# Versino1.net
KiCad netlist of a schematic drawn in EAGLE
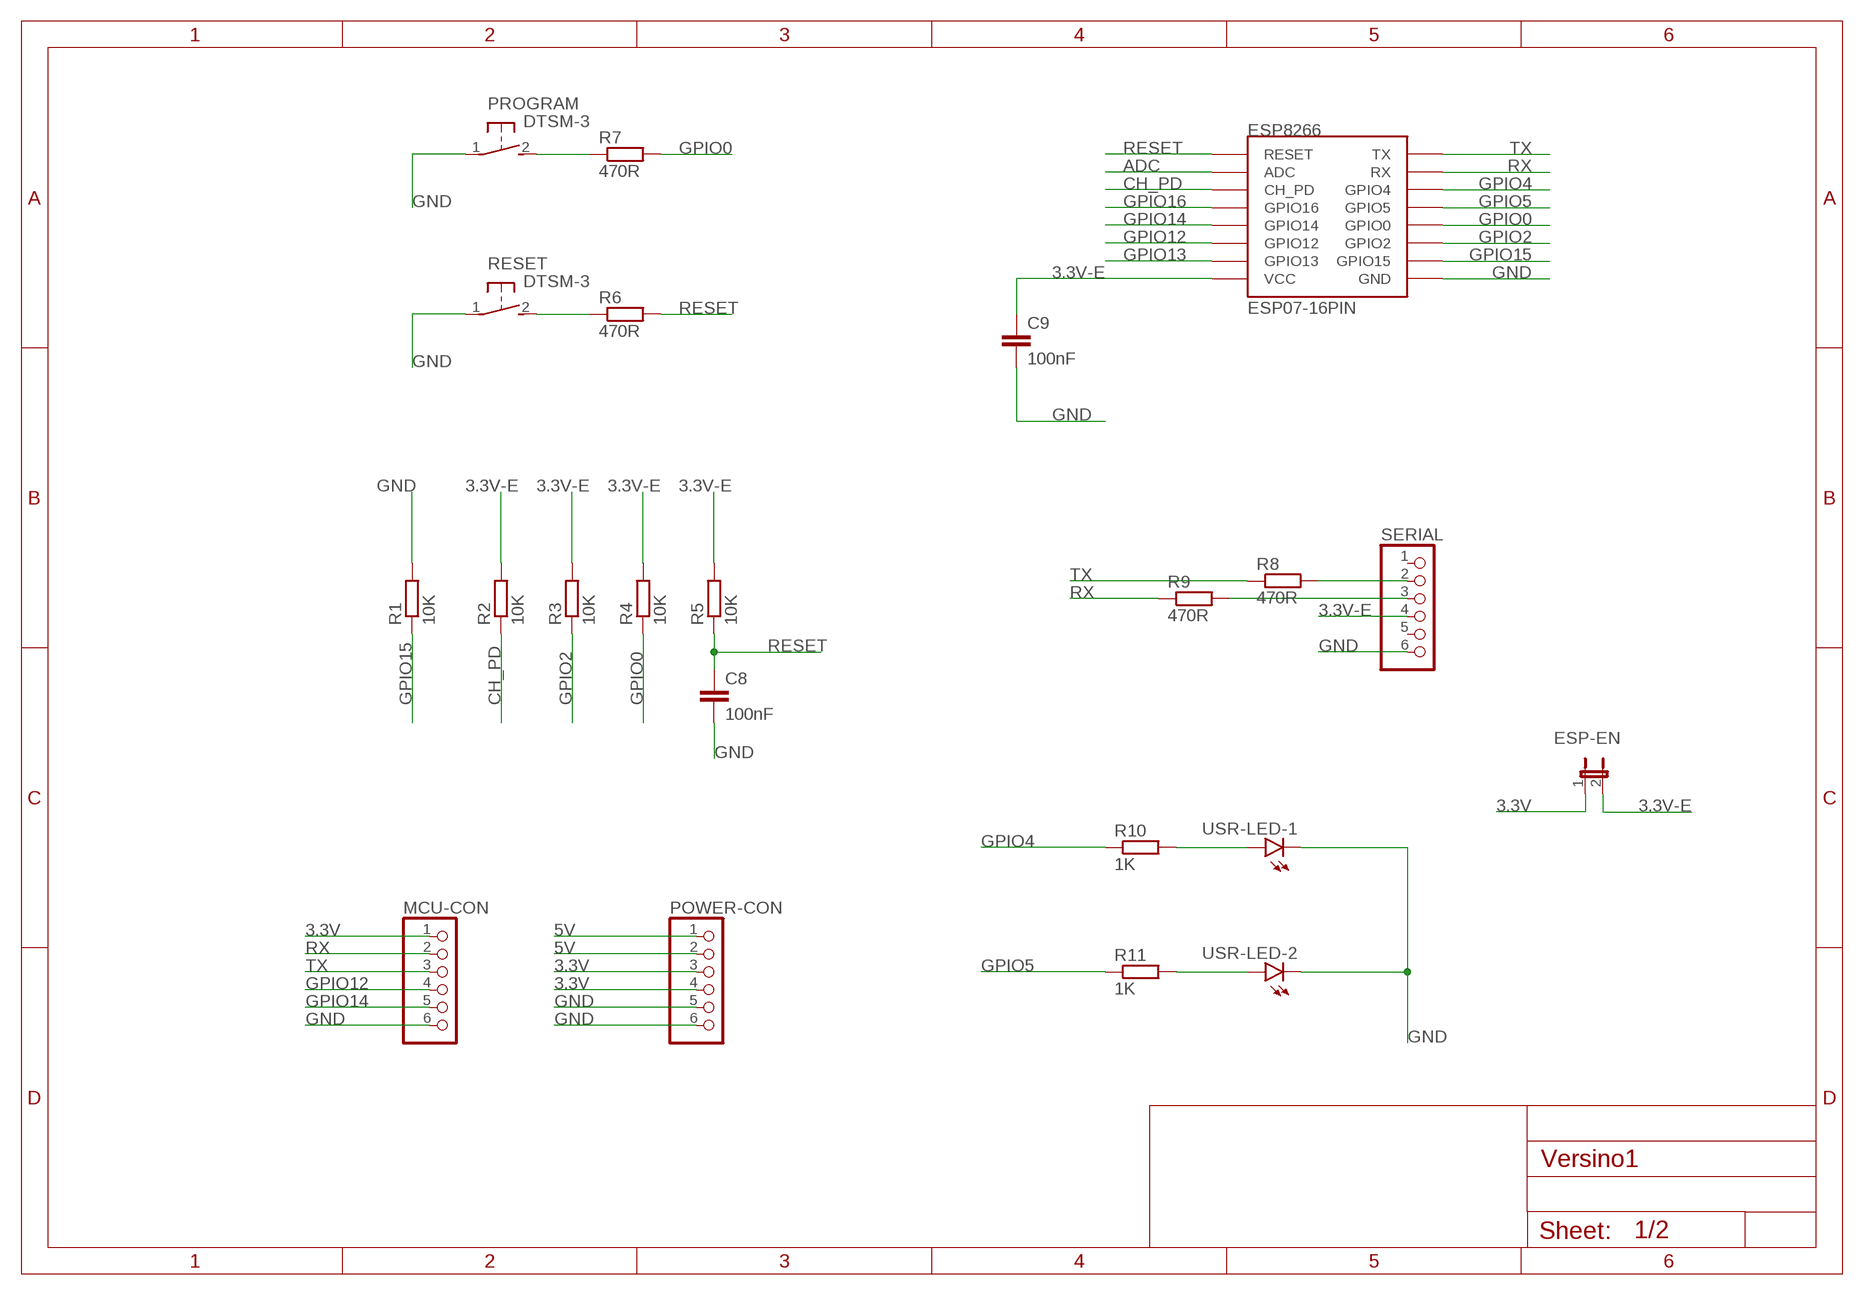
[diagram p0: schematic, sheet 1]
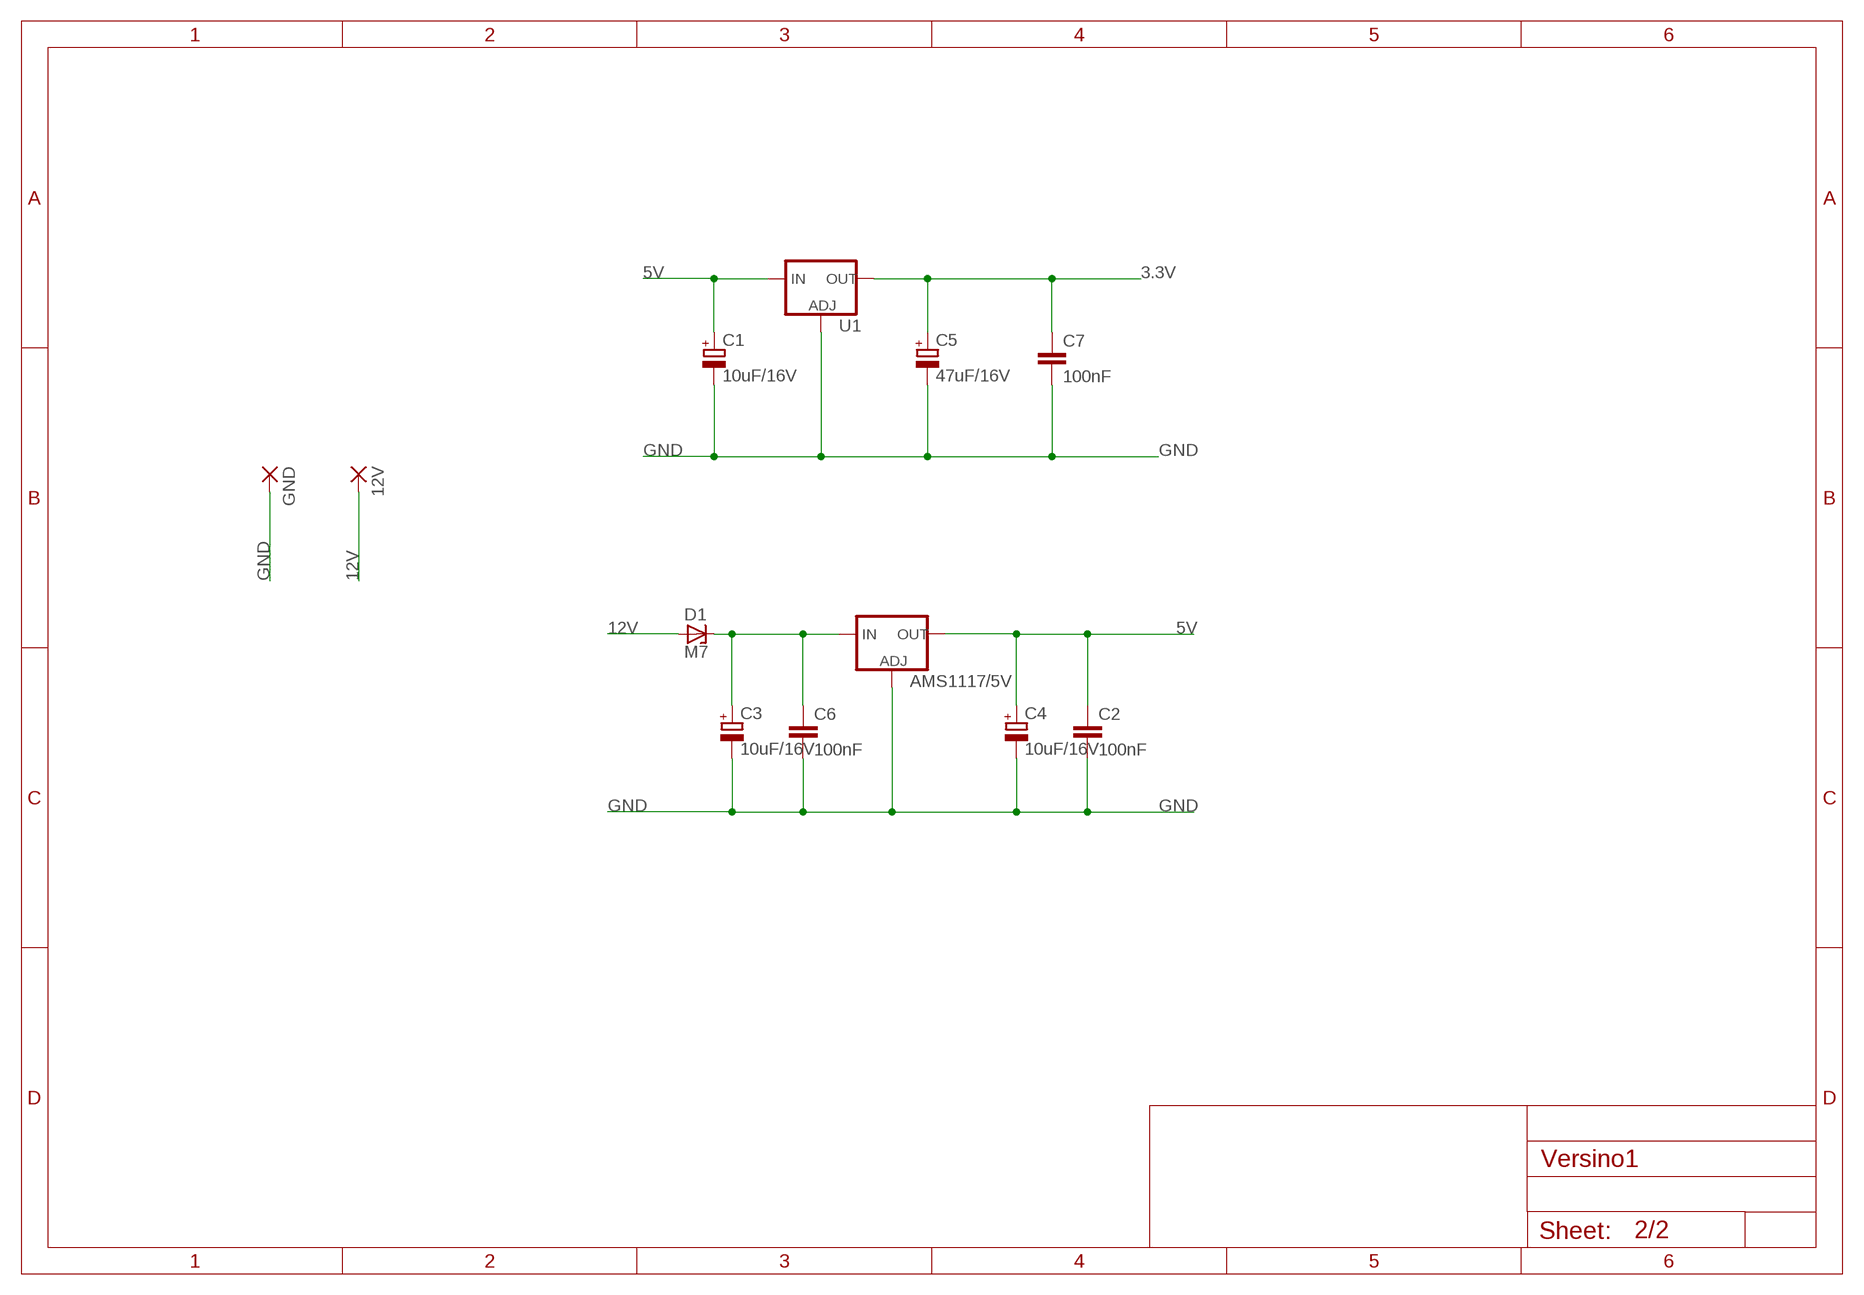
[diagram p1: schematic, sheet 2]

(export (version "E")
  (design (tool "Eeschema 10.0.6"))
  (components
    (comp (ref "12V")
      (value "SMD5")
      (footprint "eagle-import:SMD2,54-5,08")
      (libsource (lib "eagle-import") (part "SMD5"))
    )
    (comp (ref "AMS1117/5V")
      (value "V_REG_LM1117SOT223")
      (footprint "eagle-import:SOT223")
      (libsource (lib "eagle-import") (part "V_REG_LM1117SOT223"))
    )
    (comp (ref "C1")
      (value "10uF/16V")
      (footprint "eagle-import:SMC_B")
      (libsource (lib "eagle-import") (part "CPOL-EUSMCB"))
    )
    (comp (ref "C2")
      (value "100nF")
      (footprint "eagle-import:C0603")
      (libsource (lib "eagle-import") (part "C-EUC0603"))
    )
    (comp (ref "C3")
      (value "10uF/16V")
      (footprint "eagle-import:SMC_B")
      (libsource (lib "eagle-import") (part "CPOL-EUSMCB"))
    )
    (comp (ref "C4")
      (value "10uF/16V")
      (footprint "eagle-import:SMC_B")
      (libsource (lib "eagle-import") (part "CPOL-EUSMCB"))
    )
    (comp (ref "C5")
      (value "47uF/16V")
      (footprint "eagle-import:SMC_B")
      (libsource (lib "eagle-import") (part "CPOL-EUSMCB"))
    )
    (comp (ref "C6")
      (value "100nF")
      (footprint "eagle-import:C0603")
      (libsource (lib "eagle-import") (part "C-EUC0603"))
    )
    (comp (ref "C7")
      (value "100nF")
      (footprint "eagle-import:C0603")
      (libsource (lib "eagle-import") (part "C-EUC0603"))
    )
    (comp (ref "D1")
      (value "M7")
      (footprint "eagle-import:DO214AC")
      (fields (field (name "MF") "ON Semiconductor") (field (name "MPN") "1SMA5913BT3G"))
      (libsource (lib "eagle-import") (part "1SMA59BT3G13"))
    )
    (comp (ref "GND")
      (value "SMD5")
      (footprint "eagle-import:SMD2,54-5,08")
      (libsource (lib "eagle-import") (part "SMD5"))
    )
    (comp (ref "U1")
      (value "V_REG_LM1117SOT223")
      (footprint "eagle-import:SOT223")
      (libsource (lib "eagle-import") (part "V_REG_LM1117SOT223"))
    )
    (comp (ref "C8")
      (value "100nF")
      (footprint "eagle-import:C0603")
      (libsource (lib "eagle-import") (part "C-EUC0603"))
    )
    (comp (ref "C9")
      (value "100nF")
      (footprint "eagle-import:C0603")
      (libsource (lib "eagle-import") (part "C-EUC0603"))
    )
    (comp (ref "ESP-EN")
      (value "JP1E")
      (footprint "eagle-import:JP1")
      (libsource (lib "eagle-import") (part "JP1E"))
    )
    (comp (ref "ESP8266")
      (value "ESP07-16PIN")
      (footprint "eagle-import:ESP07-16PIN")
      (libsource (lib "eagle-import") (part "ESP07-16PIN"))
    )
    (comp (ref "MCU-CON")
      (value "PINHD-1X6")
      (footprint "eagle-import:1X06")
      (libsource (lib "eagle-import") (part "PINHD-1X6"))
    )
    (comp (ref "POWER-CON")
      (value "PINHD-1X6")
      (footprint "eagle-import:1X06")
      (libsource (lib "eagle-import") (part "PINHD-1X6"))
    )
    (comp (ref "PROGRAM")
      (value "DTSM-3")
      (footprint "eagle-import:DTSM-3")
      (libsource (lib "eagle-import") (part "DTSM-3"))
    )
    (comp (ref "R1")
      (value "10K")
      (footprint "eagle-import:R0603")
      (libsource (lib "eagle-import") (part "R-EU_R0603"))
    )
    (comp (ref "R2")
      (value "10K")
      (footprint "eagle-import:R0603")
      (libsource (lib "eagle-import") (part "R-EU_R0603"))
    )
    (comp (ref "R3")
      (value "10K")
      (footprint "eagle-import:R0603")
      (libsource (lib "eagle-import") (part "R-EU_R0603"))
    )
    (comp (ref "R4")
      (value "10K")
      (footprint "eagle-import:R0603")
      (libsource (lib "eagle-import") (part "R-EU_R0603"))
    )
    (comp (ref "R5")
      (value "10K")
      (footprint "eagle-import:R0603")
      (libsource (lib "eagle-import") (part "R-EU_R0603"))
    )
    (comp (ref "R6")
      (value "470R")
      (footprint "eagle-import:R0603")
      (libsource (lib "eagle-import") (part "R-EU_R0603"))
    )
    (comp (ref "R7")
      (value "470R")
      (footprint "eagle-import:R0603")
      (libsource (lib "eagle-import") (part "R-EU_R0603"))
    )
    (comp (ref "R8")
      (value "470R")
      (footprint "eagle-import:R0603")
      (libsource (lib "eagle-import") (part "R-EU_R0603"))
    )
    (comp (ref "R9")
      (value "470R")
      (footprint "eagle-import:R0603")
      (libsource (lib "eagle-import") (part "R-EU_R0603"))
    )
    (comp (ref "R10")
      (value "1K")
      (footprint "eagle-import:R0603")
      (libsource (lib "eagle-import") (part "R-EU_R0603"))
    )
    (comp (ref "R11")
      (value "1K")
      (footprint "eagle-import:R0603")
      (libsource (lib "eagle-import") (part "R-EU_R0603"))
    )
    (comp (ref "RESET")
      (value "DTSM-3")
      (footprint "eagle-import:DTSM-3")
      (libsource (lib "eagle-import") (part "DTSM-3"))
    )
    (comp (ref "SERIAL")
      (value "PINHD-1X6")
      (footprint "eagle-import:1X06")
      (libsource (lib "eagle-import") (part "PINHD-1X6"))
    )
    (comp (ref "USR-LED-1")
      (value "LEDCHIP-LED0805")
      (footprint "eagle-import:CHIP-LED0805")
      (libsource (lib "eagle-import") (part "LEDCHIP-LED0805"))
    )
    (comp (ref "USR-LED-2")
      (value "LEDCHIP-LED0805")
      (footprint "eagle-import:CHIP-LED0805")
      (libsource (lib "eagle-import") (part "LEDCHIP-LED0805"))
    )
  )
  (nets
    (net (code "1") (name "3.3V") (class "Default")
      (node (ref "C5") (pin "+") (pinfunction "+_+") (pintype "passive"))
      (node (ref "C7") (pin "1") (pinfunction "1_1") (pintype "passive"))
      (node (ref "ESP-EN") (pin "1") (pinfunction "1_1") (pintype "passive"))
      (node (ref "MCU-CON") (pin "1") (pinfunction "1_1") (pintype "passive"))
      (node (ref "POWER-CON") (pin "3") (pinfunction "3_3") (pintype "passive"))
      (node (ref "POWER-CON") (pin "4") (pinfunction "4_4") (pintype "passive"))
      (node (ref "U1") (pin "2") (pinfunction "OUT_2") (pintype "output"))
      (node (ref "U1") (pin "4") (pinfunction "OUT_4") (pintype "output"))
    )
    (net (code "2") (name "3.3V-E") (class "Default")
      (node (ref "C9") (pin "1") (pinfunction "1_1") (pintype "passive"))
      (node (ref "ESP-EN") (pin "2") (pinfunction "2_2") (pintype "passive"))
      (node (ref "ESP8266") (pin "VCC") (pinfunction "VCC_VCC") (pintype "bidirectional"))
      (node (ref "R2") (pin "2") (pinfunction "2_2") (pintype "passive"))
      (node (ref "R3") (pin "2") (pinfunction "2_2") (pintype "passive"))
      (node (ref "R4") (pin "2") (pinfunction "2_2") (pintype "passive"))
      (node (ref "R5") (pin "2") (pinfunction "2_2") (pintype "passive"))
      (node (ref "SERIAL") (pin "4") (pinfunction "4_4") (pintype "passive"))
    )
    (net (code "3") (name "5V") (class "Default")
      (node (ref "AMS1117/5V") (pin "2") (pinfunction "OUT_2") (pintype "output"))
      (node (ref "AMS1117/5V") (pin "4") (pinfunction "OUT_4") (pintype "output"))
      (node (ref "C1") (pin "+") (pinfunction "+_+") (pintype "passive"))
      (node (ref "C2") (pin "1") (pinfunction "1_1") (pintype "passive"))
      (node (ref "C4") (pin "+") (pinfunction "+_+") (pintype "passive"))
      (node (ref "POWER-CON") (pin "1") (pinfunction "1_1") (pintype "passive"))
      (node (ref "POWER-CON") (pin "2") (pinfunction "2_2") (pintype "passive"))
      (node (ref "U1") (pin "3") (pinfunction "IN_3") (pintype "input"))
    )
    (net (code "4") (name "12V") (class "Default")
      (node (ref "12V") (pin "1") (pinfunction "P_1") (pintype "passive"))
      (node (ref "D1") (pin "A") (pinfunction "A_A") (pintype "passive"))
    )
    (net (code "5") (name "ADC") (class "Default")
      (node (ref "ESP8266") (pin "ADC") (pinfunction "ADC_ADC") (pintype "bidirectional"))
    )
    (net (code "6") (name "CH_PD") (class "Default")
      (node (ref "ESP8266") (pin "CH_PD") (pinfunction "CH_PD_CH_PD") (pintype "bidirectional"))
      (node (ref "R2") (pin "1") (pinfunction "1_1") (pintype "passive"))
    )
    (net (code "7") (name "GND") (class "Default")
      (node (ref "AMS1117/5V") (pin "1") (pinfunction "ADJ_1") (pintype "input"))
      (node (ref "C1") (pin "-") (pinfunction "-_-") (pintype "passive"))
      (node (ref "C2") (pin "2") (pinfunction "2_2") (pintype "passive"))
      (node (ref "C3") (pin "-") (pinfunction "-_-") (pintype "passive"))
      (node (ref "C4") (pin "-") (pinfunction "-_-") (pintype "passive"))
      (node (ref "C5") (pin "-") (pinfunction "-_-") (pintype "passive"))
      (node (ref "C6") (pin "2") (pinfunction "2_2") (pintype "passive"))
      (node (ref "C7") (pin "2") (pinfunction "2_2") (pintype "passive"))
      (node (ref "C8") (pin "2") (pinfunction "2_2") (pintype "passive"))
      (node (ref "C9") (pin "2") (pinfunction "2_2") (pintype "passive"))
      (node (ref "ESP8266") (pin "GND") (pinfunction "GND_GND") (pintype "bidirectional"))
      (node (ref "GND") (pin "1") (pinfunction "P_1") (pintype "passive"))
      (node (ref "MCU-CON") (pin "6") (pinfunction "6_6") (pintype "passive"))
      (node (ref "POWER-CON") (pin "5") (pinfunction "5_5") (pintype "passive"))
      (node (ref "POWER-CON") (pin "6") (pinfunction "6_6") (pintype "passive"))
      (node (ref "PROGRAM") (pin "1") (pinfunction "1_1") (pintype "passive"))
      (node (ref "R1") (pin "2") (pinfunction "2_2") (pintype "passive"))
      (node (ref "RESET") (pin "1") (pinfunction "1_1") (pintype "passive"))
      (node (ref "SERIAL") (pin "6") (pinfunction "6_6") (pintype "passive"))
      (node (ref "U1") (pin "1") (pinfunction "ADJ_1") (pintype "input"))
      (node (ref "USR-LED-1") (pin "C") (pinfunction "C_C") (pintype "passive"))
      (node (ref "USR-LED-2") (pin "C") (pinfunction "C_C") (pintype "passive"))
    )
    (net (code "8") (name "GPIO0") (class "Default")
      (node (ref "ESP8266") (pin "GPIO0") (pinfunction "GPIO0_GPIO0") (pintype "bidirectional"))
      (node (ref "R4") (pin "1") (pinfunction "1_1") (pintype "passive"))
      (node (ref "R7") (pin "2") (pinfunction "2_2") (pintype "passive"))
    )
    (net (code "9") (name "GPIO2") (class "Default")
      (node (ref "ESP8266") (pin "GPIO2") (pinfunction "GPIO2_GPIO2") (pintype "bidirectional"))
      (node (ref "R3") (pin "1") (pinfunction "1_1") (pintype "passive"))
    )
    (net (code "10") (name "GPIO4") (class "Default")
      (node (ref "ESP8266") (pin "GPIO4") (pinfunction "GPIO4_GPIO4") (pintype "bidirectional"))
      (node (ref "R10") (pin "1") (pinfunction "1_1") (pintype "passive"))
    )
    (net (code "11") (name "GPIO5") (class "Default")
      (node (ref "ESP8266") (pin "GPIO5") (pinfunction "GPIO5_GPIO5") (pintype "bidirectional"))
      (node (ref "R11") (pin "1") (pinfunction "1_1") (pintype "passive"))
    )
    (net (code "12") (name "GPIO12") (class "Default")
      (node (ref "ESP8266") (pin "GPIO12") (pinfunction "GPIO12_GPIO12") (pintype "bidirectional"))
      (node (ref "MCU-CON") (pin "4") (pinfunction "4_4") (pintype "passive"))
    )
    (net (code "13") (name "GPIO13") (class "Default")
      (node (ref "ESP8266") (pin "GPIO13") (pinfunction "GPIO13_GPIO13") (pintype "bidirectional"))
    )
    (net (code "14") (name "GPIO14") (class "Default")
      (node (ref "ESP8266") (pin "GPIO14") (pinfunction "GPIO14_GPIO14") (pintype "bidirectional"))
      (node (ref "MCU-CON") (pin "5") (pinfunction "5_5") (pintype "passive"))
    )
    (net (code "15") (name "GPIO15") (class "Default")
      (node (ref "ESP8266") (pin "GPIO15") (pinfunction "GPIO15_GPIO15") (pintype "bidirectional"))
      (node (ref "R1") (pin "1") (pinfunction "1_1") (pintype "passive"))
    )
    (net (code "16") (name "GPIO16") (class "Default")
      (node (ref "ESP8266") (pin "GPIO16") (pinfunction "GPIO16_GPIO16") (pintype "bidirectional"))
    )
    (net (code "17") (name "Net-(AMS1117/5V-IN)") (class "Default")
      (node (ref "AMS1117/5V") (pin "3") (pinfunction "IN_3") (pintype "input"))
      (node (ref "C3") (pin "+") (pinfunction "+_+") (pintype "passive"))
      (node (ref "C6") (pin "1") (pinfunction "1_1") (pintype "passive"))
      (node (ref "D1") (pin "C") (pinfunction "C_C") (pintype "passive"))
    )
    (net (code "18") (name "Net-(PROGRAM-Pad2)") (class "Default")
      (node (ref "PROGRAM") (pin "2") (pinfunction "2_2") (pintype "passive"))
      (node (ref "R7") (pin "1") (pinfunction "1_1") (pintype "passive"))
    )
    (net (code "19") (name "Net-(R6-Pad1)") (class "Default")
      (node (ref "R6") (pin "1") (pinfunction "1_1") (pintype "passive"))
      (node (ref "RESET") (pin "2") (pinfunction "2_2") (pintype "passive"))
    )
    (net (code "20") (name "Net-(R8-Pad2)") (class "Default")
      (node (ref "R8") (pin "2") (pinfunction "2_2") (pintype "passive"))
      (node (ref "SERIAL") (pin "2") (pinfunction "2_2") (pintype "passive"))
    )
    (net (code "21") (name "Net-(R9-Pad2)") (class "Default")
      (node (ref "R9") (pin "2") (pinfunction "2_2") (pintype "passive"))
      (node (ref "SERIAL") (pin "3") (pinfunction "3_3") (pintype "passive"))
    )
    (net (code "22") (name "Net-(R10-Pad2)") (class "Default")
      (node (ref "R10") (pin "2") (pinfunction "2_2") (pintype "passive"))
      (node (ref "USR-LED-1") (pin "A") (pinfunction "A_A") (pintype "passive"))
    )
    (net (code "23") (name "Net-(R11-Pad2)") (class "Default")
      (node (ref "R11") (pin "2") (pinfunction "2_2") (pintype "passive"))
      (node (ref "USR-LED-2") (pin "A") (pinfunction "A_A") (pintype "passive"))
    )
    (net (code "24") (name "RESET") (class "Default")
      (node (ref "C8") (pin "1") (pinfunction "1_1") (pintype "passive"))
      (node (ref "ESP8266") (pin "REST") (pinfunction "RESET_REST") (pintype "bidirectional"))
      (node (ref "R5") (pin "1") (pinfunction "1_1") (pintype "passive"))
      (node (ref "R6") (pin "2") (pinfunction "2_2") (pintype "passive"))
    )
    (net (code "25") (name "RX") (class "Default")
      (node (ref "ESP8266") (pin "RX") (pinfunction "RX_RX") (pintype "bidirectional"))
      (node (ref "MCU-CON") (pin "2") (pinfunction "2_2") (pintype "passive"))
      (node (ref "R9") (pin "1") (pinfunction "1_1") (pintype "passive"))
    )
    (net (code "26") (name "TX") (class "Default")
      (node (ref "ESP8266") (pin "TX") (pinfunction "TX_TX") (pintype "bidirectional"))
      (node (ref "MCU-CON") (pin "3") (pinfunction "3_3") (pintype "passive"))
      (node (ref "R8") (pin "1") (pinfunction "1_1") (pintype "passive"))
    )
    (net (code "27") (name "unconnected-(SERIAL-Pad1)") (class "Default")
      (node (ref "SERIAL") (pin "1") (pinfunction "1_1") (pintype "passive"))
    )
    (net (code "28") (name "unconnected-(SERIAL-Pad5)") (class "Default")
      (node (ref "SERIAL") (pin "5") (pinfunction "5_5") (pintype "passive"))
    )
  )
)
